# Schematic.net
KiCad netlist of a schematic drawn in Altium Designer
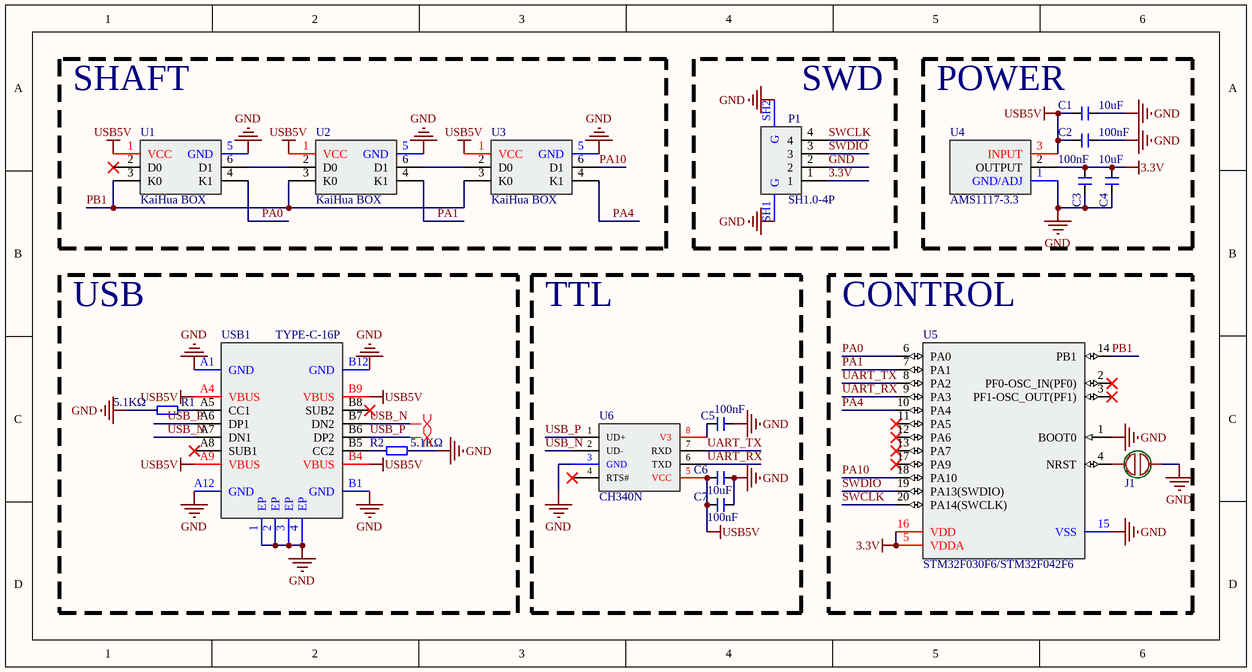
[diagram p0: Schematic.SchDoc]

(export (version "E")
  (design (tool "Eeschema 10.0.6"))
  (components
    (comp (ref "C1")
      (value "10uF")
      (footprint "C0402")
      (description "电容-0402")
      (libsource (lib "IntegratedDevices") (part "C0402"))
    )
    (comp (ref "C2")
      (value "100nF")
      (footprint "C0402")
      (description "电容-0402")
      (libsource (lib "IntegratedDevices") (part "C0402"))
    )
    (comp (ref "C3")
      (value "100nF")
      (footprint "C0402")
      (description "电容-0402")
      (libsource (lib "IntegratedDevices") (part "C0402"))
    )
    (comp (ref "C4")
      (value "10uF")
      (footprint "C0402")
      (description "电容-0402")
      (libsource (lib "IntegratedDevices") (part "C0402"))
    )
    (comp (ref "C5")
      (value "100nF")
      (footprint "C0402")
      (description "电容-0402")
      (libsource (lib "IntegratedDevices") (part "C0402"))
    )
    (comp (ref "C6")
      (value "10uF")
      (footprint "C0402")
      (description "电容-0402")
      (libsource (lib "IntegratedDevices") (part "C0402"))
    )
    (comp (ref "C7")
      (value "100nF")
      (footprint "C0402")
      (description "电容-0402")
      (libsource (lib "IntegratedDevices") (part "C0402"))
    )
    (comp (ref "J1")
      (value "Jumper")
      (footprint "R0402")
      (description "飞线，0Ω电阻")
      (libsource (lib "IntegratedDevices") (part "Jumper"))
    )
    (comp (ref "P1")
      (value "SH1.0-4P")
      (footprint "SH1.0-4P")
      (description "SH1.00mm 4P 卧贴")
      (libsource (lib "IntegratedDevices") (part "SH1.0-4P"))
    )
    (comp (ref "R1")
      (value "5.1KΩ")
      (footprint "R0402")
      (description "电阻-0402")
      (libsource (lib "IntegratedDevices") (part "R0402"))
    )
    (comp (ref "R2")
      (value "5.1KΩ")
      (footprint "R0402")
      (description "电阻-0402")
      (libsource (lib "IntegratedDevices") (part "R0402"))
    )
    (comp (ref "U1")
      (value "KaiHua BOX")
      (footprint "凯华轴座+3528反贴灯")
      (description "凯华轴座+3528反贴灯，缺口在右下")
      (libsource (lib "IntegratedDevices") (part "KaiHua BOX"))
    )
    (comp (ref "U2")
      (value "KaiHua BOX")
      (footprint "凯华轴座+3528反贴灯")
      (description "凯华轴座+3528反贴灯，缺口在右下")
      (libsource (lib "IntegratedDevices") (part "KaiHua BOX"))
    )
    (comp (ref "U3")
      (value "KaiHua BOX")
      (footprint "凯华轴座+3528反贴灯")
      (description "凯华轴座+3528反贴灯，缺口在右下")
      (libsource (lib "IntegratedDevices") (part "KaiHua BOX"))
    )
    (comp (ref "U4")
      (value "AMS1117-3.3")
      (footprint "SOT-89")
      (description "电源IC 降压IC 线性稳压LDO SOT-89封装")
      (libsource (lib "IntegratedDevices") (part "AMS1117-3.3 89"))
    )
    (comp (ref "U5")
      (value "STM32F030F6/STM32F042F6")
      (footprint "TSSOP-20")
      (fields (field (name "PARTNUMBER") "STM32F030F4P6"))
      (libsource (lib "IntegratedDevices") (part "STM32F030F4P6"))
    )
    (comp (ref "U6")
      (value "CH340N")
      (footprint "SOP-8")
      (description "CH340N通讯芯片")
      (libsource (lib "IntegratedDevices") (part "CH340N"))
    )
    (comp (ref "USB1")
      (value "TYPE-C-16P")
      (footprint "TYPE-C-KH Female_LieDown_16P")
      (description "Type-C母座_卧贴_16P")
      (libsource (lib "IntegratedDevices") (part "TYPE-C-KH Female_LieDown_16P"))
    )
  )
  (nets
    (net (code "1") (name "/PA0") (class "Default")
      (node (ref "U1") (pin "4") (pinfunction "K1_4") (pintype "passive"))
      (node (ref "U5") (pin "6") (pinfunction "PA0_6") (pintype "bidirectional"))
    )
    (net (code "2") (name "/PA1") (class "Default")
      (node (ref "U2") (pin "4") (pinfunction "K1_4") (pintype "passive"))
      (node (ref "U5") (pin "7") (pinfunction "PA1_7") (pintype "bidirectional"))
    )
    (net (code "3") (name "/PA4") (class "Default")
      (node (ref "U3") (pin "4") (pinfunction "K1_4") (pintype "passive"))
      (node (ref "U5") (pin "10") (pinfunction "PA4_10") (pintype "bidirectional"))
    )
    (net (code "4") (name "/PA10") (class "Default")
      (node (ref "U3") (pin "6") (pinfunction "D1_6") (pintype "passive"))
      (node (ref "U5") (pin "18") (pinfunction "PA10_18") (pintype "bidirectional"))
    )
    (net (code "5") (name "/PB1") (class "Default")
      (node (ref "U1") (pin "3") (pinfunction "K0_3") (pintype "passive"))
      (node (ref "U2") (pin "3") (pinfunction "K0_3") (pintype "passive"))
      (node (ref "U3") (pin "3") (pinfunction "K0_3") (pintype "passive"))
      (node (ref "U5") (pin "14") (pinfunction "PB1_14") (pintype "bidirectional"))
    )
    (net (code "6") (name "/SWCLK") (class "Default")
      (node (ref "P1") (pin "4") (pinfunction "4_4") (pintype "passive"))
      (node (ref "U5") (pin "20") (pinfunction "PA14(SWCLK)_20") (pintype "bidirectional"))
    )
    (net (code "7") (name "/SWDIO") (class "Default")
      (node (ref "P1") (pin "3") (pinfunction "3_3") (pintype "passive"))
      (node (ref "U5") (pin "19") (pinfunction "PA13(SWDIO)_19") (pintype "bidirectional"))
    )
    (net (code "8") (name "/UART_RX") (class "Default")
      (node (ref "U5") (pin "9") (pinfunction "PA3_9") (pintype "bidirectional"))
      (node (ref "U6") (pin "6") (pinfunction "TXD_6") (pintype "passive"))
    )
    (net (code "9") (name "/UART_TX") (class "Default")
      (node (ref "U5") (pin "8") (pinfunction "PA2_8") (pintype "bidirectional"))
      (node (ref "U6") (pin "7") (pinfunction "RXD_7") (pintype "passive"))
    )
    (net (code "10") (name "/USB_N") (class "Default")
      (node (ref "U6") (pin "2") (pinfunction "UD-_2") (pintype "passive"))
      (node (ref "USB1") (pin "A7") (pinfunction "DN1_A7") (pintype "passive"))
      (node (ref "USB1") (pin "B7") (pinfunction "DN2_B7") (pintype "passive"))
    )
    (net (code "11") (name "/USB_P") (class "Default")
      (node (ref "U6") (pin "1") (pinfunction "UD+_1") (pintype "passive"))
      (node (ref "USB1") (pin "A6") (pinfunction "DP1_A6") (pintype "passive"))
      (node (ref "USB1") (pin "B6") (pinfunction "DP2_B6") (pintype "passive"))
    )
    (net (code "12") (name "3.3V") (class "Default")
      (node (ref "C3") (pin "2") (pinfunction "2_2") (pintype "passive"))
      (node (ref "C4") (pin "2") (pinfunction "2_2") (pintype "passive"))
      (node (ref "P1") (pin "1") (pinfunction "1_1") (pintype "passive"))
      (node (ref "U4") (pin "2") (pinfunction "OUTPUT_2") (pintype "passive"))
      (node (ref "U5") (pin "16") (pinfunction "VDD_16") (pintype "power_in"))
      (node (ref "U5") (pin "5") (pinfunction "VDDA_5") (pintype "power_in"))
    )
    (net (code "13") (name "GND") (class "Default")
      (node (ref "C1") (pin "2") (pinfunction "2_2") (pintype "passive"))
      (node (ref "C2") (pin "2") (pinfunction "2_2") (pintype "passive"))
      (node (ref "C3") (pin "1") (pinfunction "1_1") (pintype "passive"))
      (node (ref "C4") (pin "1") (pinfunction "1_1") (pintype "passive"))
      (node (ref "C5") (pin "2") (pinfunction "2_2") (pintype "passive"))
      (node (ref "C6") (pin "2") (pinfunction "2_2") (pintype "passive"))
      (node (ref "C7") (pin "2") (pinfunction "2_2") (pintype "passive"))
      (node (ref "J1") (pin "2") (pinfunction "2_2") (pintype "passive"))
      (node (ref "P1") (pin "2") (pinfunction "2_2") (pintype "passive"))
      (node (ref "P1") (pin "SH1") (pinfunction "G_SH1") (pintype "passive"))
      (node (ref "P1") (pin "SH2") (pinfunction "G_SH2") (pintype "passive"))
      (node (ref "R1") (pin "1") (pinfunction "1_1") (pintype "passive"))
      (node (ref "R2") (pin "2") (pinfunction "2_2") (pintype "passive"))
      (node (ref "U1") (pin "5") (pinfunction "GND_5") (pintype "passive"))
      (node (ref "U2") (pin "5") (pinfunction "GND_5") (pintype "passive"))
      (node (ref "U3") (pin "5") (pinfunction "GND_5") (pintype "passive"))
      (node (ref "U4") (pin "1") (pinfunction "GND/ADJ_1") (pintype "passive"))
      (node (ref "U5") (pin "1") (pinfunction "BOOT0_1") (pintype "input"))
      (node (ref "U5") (pin "15") (pinfunction "VSS_15") (pintype "power_in"))
      (node (ref "U6") (pin "3") (pinfunction "GND_3") (pintype "passive"))
      (node (ref "USB1") (pin "1") (pinfunction "EP_1") (pintype "passive"))
      (node (ref "USB1") (pin "2") (pinfunction "EP_2") (pintype "passive"))
      (node (ref "USB1") (pin "3") (pinfunction "EP_3") (pintype "passive"))
      (node (ref "USB1") (pin "4") (pinfunction "EP_4") (pintype "passive"))
      (node (ref "USB1") (pin "A1") (pinfunction "GND_A1") (pintype "passive"))
      (node (ref "USB1") (pin "A12") (pinfunction "GND_A12") (pintype "passive"))
      (node (ref "USB1") (pin "B1") (pinfunction "GND_B1") (pintype "passive"))
      (node (ref "USB1") (pin "B12") (pinfunction "GND_B12") (pintype "passive"))
    )
    (net (code "14") (name "Net-(U1-D1)") (class "Default")
      (node (ref "U1") (pin "6") (pinfunction "D1_6") (pintype "passive"))
      (node (ref "U2") (pin "2") (pinfunction "D0_2") (pintype "passive"))
    )
    (net (code "15") (name "Net-(U2-D1)") (class "Default")
      (node (ref "U2") (pin "6") (pinfunction "D1_6") (pintype "passive"))
      (node (ref "U3") (pin "2") (pinfunction "D0_2") (pintype "passive"))
    )
    (net (code "16") (name "Net-(U5-NRST)") (class "Default")
      (node (ref "J1") (pin "1") (pinfunction "1_1") (pintype "passive"))
      (node (ref "U5") (pin "4") (pinfunction "NRST_4") (pintype "bidirectional"))
    )
    (net (code "17") (name "Net-(U6-V3)") (class "Default")
      (node (ref "C5") (pin "1") (pinfunction "1_1") (pintype "passive"))
      (node (ref "U6") (pin "8") (pinfunction "V3_8") (pintype "passive"))
    )
    (net (code "18") (name "Net-(USB1-CC1)") (class "Default")
      (node (ref "R1") (pin "2") (pinfunction "2_2") (pintype "passive"))
      (node (ref "USB1") (pin "A5") (pinfunction "CC1_A5") (pintype "passive"))
    )
    (net (code "19") (name "Net-(USB1-CC2)") (class "Default")
      (node (ref "R2") (pin "1") (pinfunction "1_1") (pintype "passive"))
      (node (ref "USB1") (pin "B5") (pinfunction "CC2_B5") (pintype "passive"))
    )
    (net (code "20") (name "USB5V") (class "Default")
      (node (ref "C1") (pin "1") (pinfunction "1_1") (pintype "passive"))
      (node (ref "C2") (pin "1") (pinfunction "1_1") (pintype "passive"))
      (node (ref "C6") (pin "1") (pinfunction "1_1") (pintype "passive"))
      (node (ref "C7") (pin "1") (pinfunction "1_1") (pintype "passive"))
      (node (ref "U1") (pin "1") (pinfunction "VCC_1") (pintype "passive"))
      (node (ref "U2") (pin "1") (pinfunction "VCC_1") (pintype "passive"))
      (node (ref "U3") (pin "1") (pinfunction "VCC_1") (pintype "passive"))
      (node (ref "U4") (pin "3") (pinfunction "INPUT_3") (pintype "passive"))
      (node (ref "U6") (pin "5") (pinfunction "VCC_5") (pintype "passive"))
      (node (ref "USB1") (pin "A4") (pinfunction "VBUS_A4") (pintype "passive"))
      (node (ref "USB1") (pin "A9") (pinfunction "VBUS_A9") (pintype "passive"))
      (node (ref "USB1") (pin "B4") (pinfunction "VBUS_B4") (pintype "passive"))
      (node (ref "USB1") (pin "B9") (pinfunction "VBUS_B9") (pintype "passive"))
    )
    (net (code "21") (name "unconnected-(U1-D0-Pad2)") (class "Default")
      (node (ref "U1") (pin "2") (pinfunction "D0_2") (pintype "passive+no_connect"))
    )
    (net (code "22") (name "unconnected-(U5-PA5-Pad11)") (class "Default")
      (node (ref "U5") (pin "11") (pinfunction "PA5_11") (pintype "bidirectional+no_connect"))
    )
    (net (code "23") (name "unconnected-(U5-PA6-Pad12)") (class "Default")
      (node (ref "U5") (pin "12") (pinfunction "PA6_12") (pintype "bidirectional+no_connect"))
    )
    (net (code "24") (name "unconnected-(U5-PA7-Pad13)") (class "Default")
      (node (ref "U5") (pin "13") (pinfunction "PA7_13") (pintype "bidirectional+no_connect"))
    )
    (net (code "25") (name "unconnected-(U5-PA9-Pad17)") (class "Default")
      (node (ref "U5") (pin "17") (pinfunction "PA9_17") (pintype "bidirectional+no_connect"))
    )
    (net (code "26") (name "unconnected-(U5-PF0-OSC_IN(PF0)-Pad2)") (class "Default")
      (node (ref "U5") (pin "2") (pinfunction "PF0-OSC_IN(PF0)_2") (pintype "bidirectional+no_connect"))
    )
    (net (code "27") (name "unconnected-(U5-PF1-OSC_OUT(PF1)-Pad3)") (class "Default")
      (node (ref "U5") (pin "3") (pinfunction "PF1-OSC_OUT(PF1)_3") (pintype "bidirectional+no_connect"))
    )
    (net (code "28") (name "unconnected-(U6-RTS#-Pad4)") (class "Default")
      (node (ref "U6") (pin "4") (pinfunction "RTS#_4") (pintype "passive+no_connect"))
    )
    (net (code "29") (name "unconnected-(USB1-SUB1-PadA8)") (class "Default")
      (node (ref "USB1") (pin "A8") (pinfunction "SUB1_A8") (pintype "passive+no_connect"))
    )
    (net (code "30") (name "unconnected-(USB1-SUB2-PadB8)") (class "Default")
      (node (ref "USB1") (pin "B8") (pinfunction "SUB2_B8") (pintype "passive+no_connect"))
    )
  )
)
